# avr.net
KiCad netlist of a schematic drawn in EAGLE
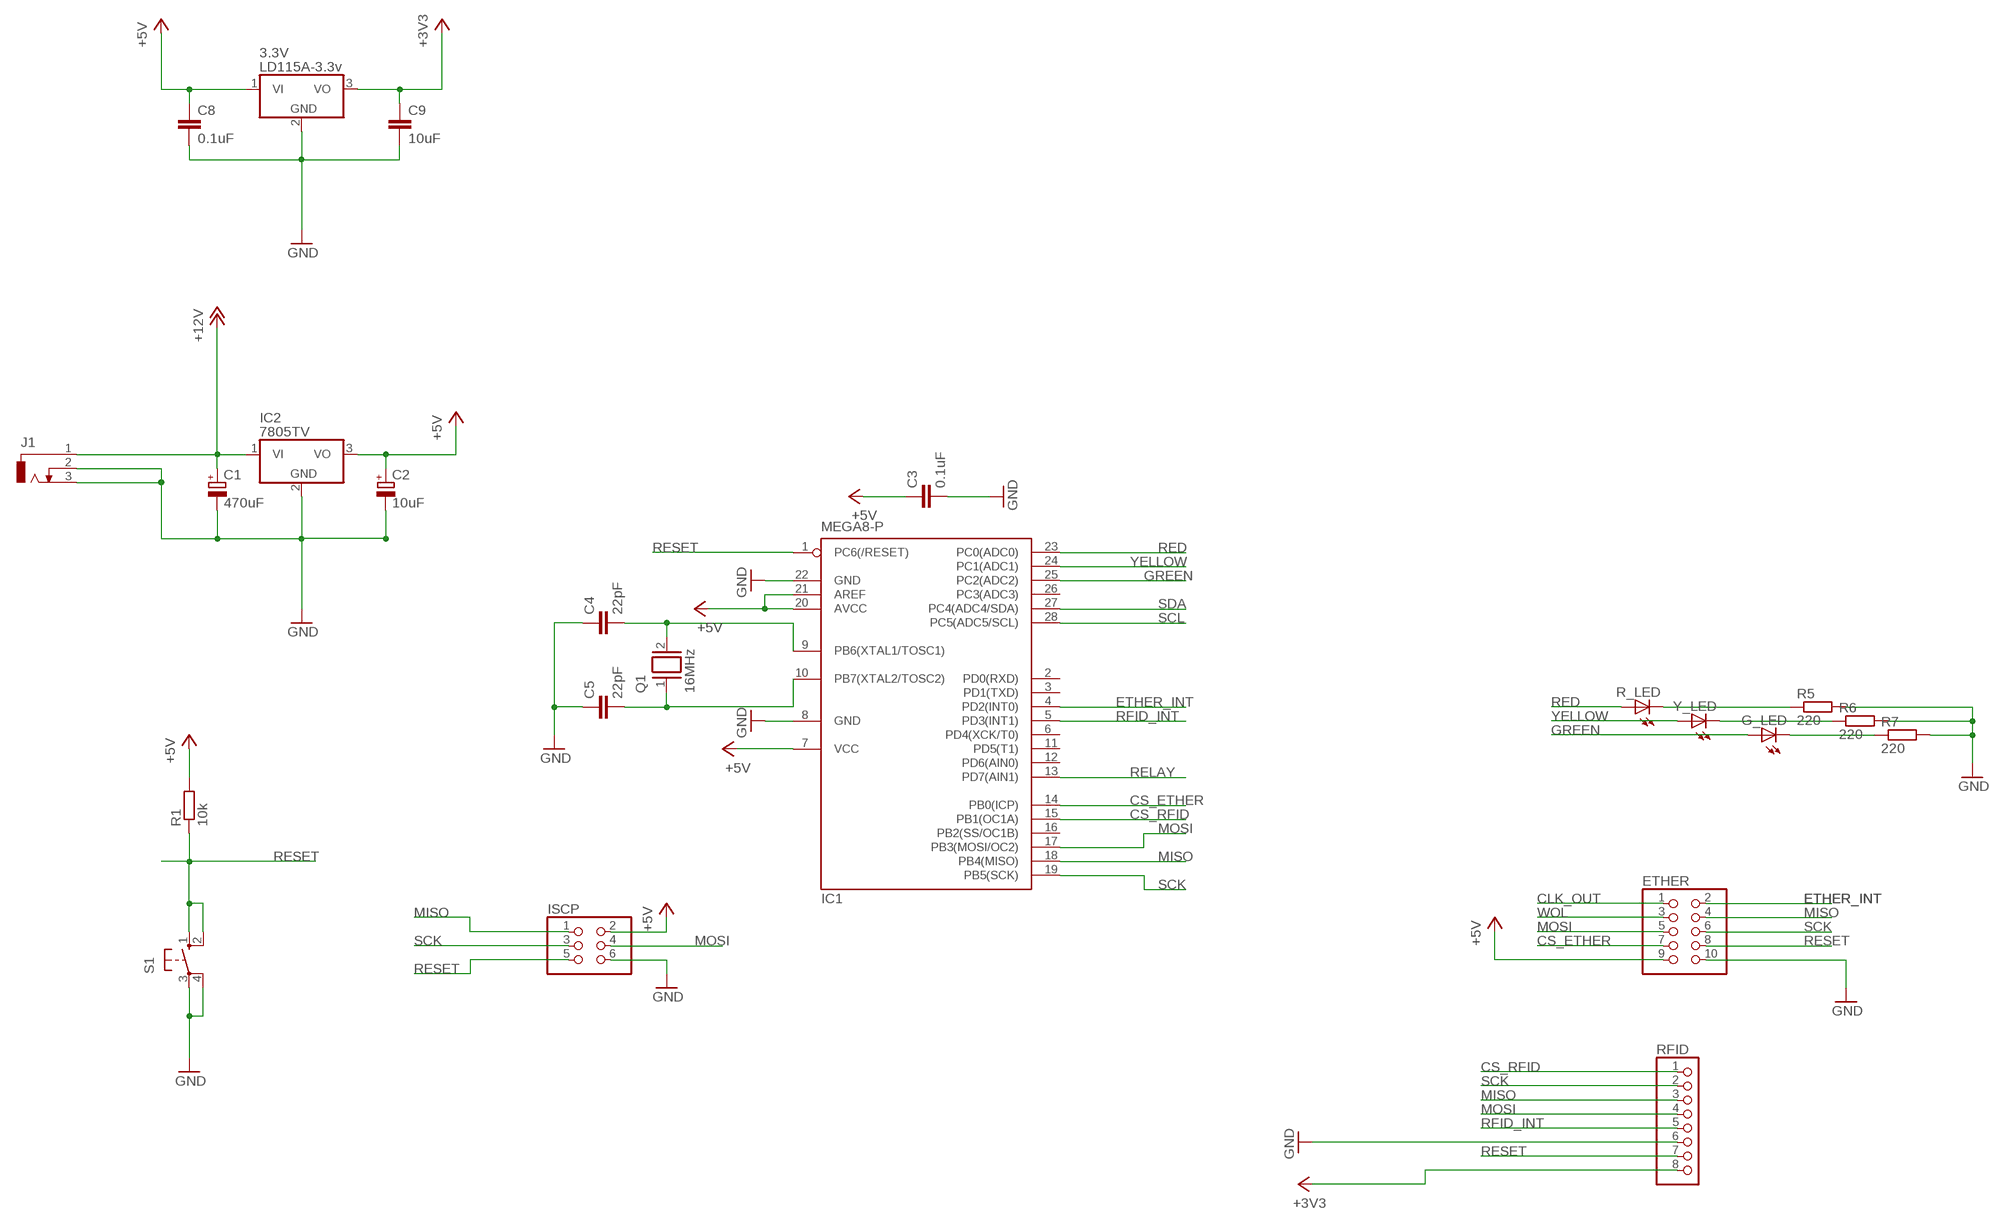
[diagram p0: schematic, sheet 1]

(export (version "E")
  (design (tool "Eeschema 10.0.6"))
  (components
    (comp (ref "3.3V")
      (value "LD115A-3.3v")
      (footprint "eagle-import:TO220V")
      (libsource (lib "eagle-import") (part "78TV05"))
    )
    (comp (ref "C1")
      (value "470uF")
      (footprint "eagle-import:E3,5-10")
      (libsource (lib "eagle-import") (part "CPOL-EUE3.5-10"))
    )
    (comp (ref "C2")
      (value "10uF")
      (footprint "eagle-import:E3,5-10")
      (libsource (lib "eagle-import") (part "CPOL-EUE3.5-10"))
    )
    (comp (ref "C3")
      (value "0.1uF")
      (footprint "eagle-import:C050-025X075")
      (libsource (lib "eagle-import") (part "C-EU050-025X075"))
    )
    (comp (ref "C4")
      (value "22pF")
      (footprint "eagle-import:C050-025X075")
      (libsource (lib "eagle-import") (part "C-EU050-025X075"))
    )
    (comp (ref "C5")
      (value "22pF")
      (footprint "eagle-import:C050-025X075")
      (libsource (lib "eagle-import") (part "C-EU050-025X075"))
    )
    (comp (ref "C8")
      (value "0.1uF")
      (footprint "eagle-import:C050-025X075")
      (libsource (lib "eagle-import") (part "C-EU050-025X075"))
    )
    (comp (ref "C9")
      (value "10uF")
      (footprint "eagle-import:C050-025X075")
      (libsource (lib "eagle-import") (part "C-EU050-025X075"))
    )
    (comp (ref "ETHER")
      (value "PINHD-2X5")
      (footprint "eagle-import:2X05")
      (libsource (lib "eagle-import") (part "PINHD-2X5"))
    )
    (comp (ref "G_LED")
      (value "LED5MM")
      (footprint "eagle-import:LED5MM")
      (libsource (lib "eagle-import") (part "LED5MM"))
    )
    (comp (ref "IC1")
      (value "MEGA8-P")
      (footprint "eagle-import:DIL28-3")
      (libsource (lib "eagle-import") (part "MEGA8-P"))
    )
    (comp (ref "IC2")
      (value "7805TV")
      (footprint "eagle-import:TO220V")
      (libsource (lib "eagle-import") (part "78TV05"))
    )
    (comp (ref "ISCP")
      (value "PINHD-2X3")
      (footprint "eagle-import:2X03")
      (libsource (lib "eagle-import") (part "PINHD-2X3"))
    )
    (comp (ref "J1")
      (value "DCJ0303")
      (footprint "eagle-import:DCJ0303")
      (libsource (lib "eagle-import") (part "DCJ0303"))
    )
    (comp (ref "Q1")
      (value "16MHz")
      (footprint "eagle-import:QS")
      (libsource (lib "eagle-import") (part "XTAL/S"))
    )
    (comp (ref "R1")
      (value "10k")
      (footprint "eagle-import:0207_10")
      (libsource (lib "eagle-import") (part "R-EU_0207/10"))
    )
    (comp (ref "R5")
      (value "220")
      (footprint "eagle-import:0207_10")
      (libsource (lib "eagle-import") (part "R-EU_0207/10"))
    )
    (comp (ref "R6")
      (value "220")
      (footprint "eagle-import:0207_10")
      (libsource (lib "eagle-import") (part "R-EU_0207/10"))
    )
    (comp (ref "R7")
      (value "220")
      (footprint "eagle-import:0207_10")
      (libsource (lib "eagle-import") (part "R-EU_0207/10"))
    )
    (comp (ref "RFID")
      (value "PINHD-1X8")
      (footprint "eagle-import:1X08")
      (libsource (lib "eagle-import") (part "PINHD-1X8"))
    )
    (comp (ref "R_LED")
      (value "LED5MM")
      (footprint "eagle-import:LED5MM")
      (libsource (lib "eagle-import") (part "LED5MM"))
    )
    (comp (ref "S1")
      (value "10-XX")
      (footprint "eagle-import:B3F-10XX")
      (fields (field (name "MPN") "B3F-1000"))
      (libsource (lib "eagle-import") (part "10-XX"))
    )
    (comp (ref "Y_LED")
      (value "LED5MM")
      (footprint "eagle-import:LED5MM")
      (libsource (lib "eagle-import") (part "LED5MM"))
    )
  )
  (nets
    (net (code "1") (name "+3V3") (class "Default")
      (node (ref "3.3V") (pin "3") (pinfunction "VO_3") (pintype "passive"))
      (node (ref "C9") (pin "1") (pinfunction "1_1") (pintype "passive"))
      (node (ref "RFID") (pin "8") (pinfunction "8_8") (pintype "passive"))
    )
    (net (code "2") (name "+5V") (class "Default")
      (node (ref "3.3V") (pin "1") (pinfunction "VI_1") (pintype "input"))
      (node (ref "C2") (pin "+") (pinfunction "+_+") (pintype "passive"))
      (node (ref "C3") (pin "1") (pinfunction "1_1") (pintype "passive"))
      (node (ref "C8") (pin "1") (pinfunction "1_1") (pintype "passive"))
      (node (ref "ETHER") (pin "9") (pinfunction "9_9") (pintype "passive"))
      (node (ref "IC1") (pin "20") (pinfunction "AVCC_20") (pintype "power_in"))
      (node (ref "IC1") (pin "21") (pinfunction "AREF_21") (pintype "passive"))
      (node (ref "IC1") (pin "7") (pinfunction "VCC_7") (pintype "power_in"))
      (node (ref "IC2") (pin "3") (pinfunction "VO_3") (pintype "passive"))
      (node (ref "ISCP") (pin "2") (pinfunction "2_2") (pintype "passive"))
      (node (ref "R1") (pin "2") (pinfunction "2_2") (pintype "passive"))
    )
    (net (code "3") (name "+12V") (class "Default")
      (node (ref "C1") (pin "+") (pinfunction "+_+") (pintype "passive"))
      (node (ref "IC2") (pin "1") (pinfunction "VI_1") (pintype "input"))
      (node (ref "J1") (pin "1") (pinfunction "1_1") (pintype "passive"))
    )
    (net (code "4") (name "/CLK_OUT") (class "Default")
      (node (ref "ETHER") (pin "1") (pinfunction "1_1") (pintype "passive"))
    )
    (net (code "5") (name "/CS_ETHER") (class "Default")
      (node (ref "ETHER") (pin "7") (pinfunction "7_7") (pintype "passive"))
      (node (ref "IC1") (pin "14") (pinfunction "PB0(ICP)_14") (pintype "bidirectional"))
    )
    (net (code "6") (name "/CS_RFID") (class "Default")
      (node (ref "IC1") (pin "15") (pinfunction "PB1(OC1A)_15") (pintype "bidirectional"))
      (node (ref "RFID") (pin "1") (pinfunction "1_1") (pintype "passive"))
    )
    (net (code "7") (name "/ETHER_INT") (class "Default")
      (node (ref "ETHER") (pin "2") (pinfunction "2_2") (pintype "passive"))
      (node (ref "IC1") (pin "4") (pinfunction "PD2(INT0)_4") (pintype "bidirectional"))
    )
    (net (code "8") (name "/GREEN") (class "Default")
      (node (ref "G_LED") (pin "A") (pinfunction "A_A") (pintype "passive"))
      (node (ref "IC1") (pin "25") (pinfunction "PC2(ADC2)_25") (pintype "bidirectional"))
    )
    (net (code "9") (name "/MISO") (class "Default")
      (node (ref "ETHER") (pin "4") (pinfunction "4_4") (pintype "passive"))
      (node (ref "IC1") (pin "18") (pinfunction "PB4(MISO)_18") (pintype "bidirectional"))
      (node (ref "ISCP") (pin "1") (pinfunction "1_1") (pintype "passive"))
      (node (ref "RFID") (pin "3") (pinfunction "3_3") (pintype "passive"))
    )
    (net (code "10") (name "/MOSI") (class "Default")
      (node (ref "ETHER") (pin "5") (pinfunction "5_5") (pintype "passive"))
      (node (ref "IC1") (pin "17") (pinfunction "PB3(MOSI/OC2)_17") (pintype "bidirectional"))
      (node (ref "ISCP") (pin "4") (pinfunction "4_4") (pintype "passive"))
      (node (ref "RFID") (pin "4") (pinfunction "4_4") (pintype "passive"))
    )
    (net (code "11") (name "/RED") (class "Default")
      (node (ref "IC1") (pin "23") (pinfunction "PC0(ADC0)_23") (pintype "bidirectional"))
      (node (ref "R_LED") (pin "A") (pinfunction "A_A") (pintype "passive"))
    )
    (net (code "12") (name "/RELAY") (class "Default")
      (node (ref "IC1") (pin "13") (pinfunction "PD7(AIN1)_13") (pintype "bidirectional"))
    )
    (net (code "13") (name "/RESET") (class "Default")
      (node (ref "ETHER") (pin "8") (pinfunction "8_8") (pintype "passive"))
      (node (ref "IC1") (pin "1") (pinfunction "PC6(/RESET)_1") (pintype "bidirectional"))
      (node (ref "ISCP") (pin "5") (pinfunction "5_5") (pintype "passive"))
      (node (ref "R1") (pin "1") (pinfunction "1_1") (pintype "passive"))
      (node (ref "RFID") (pin "7") (pinfunction "7_7") (pintype "passive"))
      (node (ref "S1") (pin "1") (pinfunction "S_1") (pintype "passive"))
      (node (ref "S1") (pin "2") (pinfunction "S1_2") (pintype "passive"))
    )
    (net (code "14") (name "/RFID_INT") (class "Default")
      (node (ref "IC1") (pin "5") (pinfunction "PD3(INT1)_5") (pintype "bidirectional"))
      (node (ref "RFID") (pin "5") (pinfunction "5_5") (pintype "passive"))
    )
    (net (code "15") (name "/SCK") (class "Default")
      (node (ref "ETHER") (pin "6") (pinfunction "6_6") (pintype "passive"))
      (node (ref "IC1") (pin "19") (pinfunction "PB5(SCK)_19") (pintype "bidirectional"))
      (node (ref "ISCP") (pin "3") (pinfunction "3_3") (pintype "passive"))
      (node (ref "RFID") (pin "2") (pinfunction "2_2") (pintype "passive"))
    )
    (net (code "16") (name "/SCL") (class "Default")
      (node (ref "IC1") (pin "28") (pinfunction "PC5(ADC5/SCL)_28") (pintype "bidirectional"))
    )
    (net (code "17") (name "/SDA") (class "Default")
      (node (ref "IC1") (pin "27") (pinfunction "PC4(ADC4/SDA)_27") (pintype "bidirectional"))
    )
    (net (code "18") (name "/WOL") (class "Default")
      (node (ref "ETHER") (pin "3") (pinfunction "3_3") (pintype "passive"))
    )
    (net (code "19") (name "/YELLOW") (class "Default")
      (node (ref "IC1") (pin "24") (pinfunction "PC1(ADC1)_24") (pintype "bidirectional"))
      (node (ref "Y_LED") (pin "A") (pinfunction "A_A") (pintype "passive"))
    )
    (net (code "20") (name "GND") (class "Default")
      (node (ref "3.3V") (pin "2") (pinfunction "GND_2") (pintype "passive"))
      (node (ref "C1") (pin "-") (pinfunction "-_-") (pintype "passive"))
      (node (ref "C2") (pin "-") (pinfunction "-_-") (pintype "passive"))
      (node (ref "C3") (pin "2") (pinfunction "2_2") (pintype "passive"))
      (node (ref "C4") (pin "1") (pinfunction "1_1") (pintype "passive"))
      (node (ref "C5") (pin "1") (pinfunction "1_1") (pintype "passive"))
      (node (ref "C8") (pin "2") (pinfunction "2_2") (pintype "passive"))
      (node (ref "C9") (pin "2") (pinfunction "2_2") (pintype "passive"))
      (node (ref "ETHER") (pin "10") (pinfunction "10_10") (pintype "passive"))
      (node (ref "IC1") (pin "22") (pinfunction "GND_22") (pintype "power_in"))
      (node (ref "IC1") (pin "8") (pinfunction "GND_8") (pintype "power_in"))
      (node (ref "IC2") (pin "2") (pinfunction "GND_2") (pintype "passive"))
      (node (ref "ISCP") (pin "6") (pinfunction "6_6") (pintype "passive"))
      (node (ref "J1") (pin "2") (pinfunction "2_2") (pintype "passive"))
      (node (ref "J1") (pin "3") (pinfunction "3_3") (pintype "passive"))
      (node (ref "R5") (pin "2") (pinfunction "2_2") (pintype "passive"))
      (node (ref "R6") (pin "2") (pinfunction "2_2") (pintype "passive"))
      (node (ref "R7") (pin "2") (pinfunction "2_2") (pintype "passive"))
      (node (ref "RFID") (pin "6") (pinfunction "6_6") (pintype "passive"))
      (node (ref "S1") (pin "3") (pinfunction "P_3") (pintype "passive"))
      (node (ref "S1") (pin "4") (pinfunction "P1_4") (pintype "passive"))
    )
    (net (code "21") (name "Net-(G_LED-C)") (class "Default")
      (node (ref "G_LED") (pin "K") (pinfunction "C_K") (pintype "passive"))
      (node (ref "R7") (pin "1") (pinfunction "1_1") (pintype "passive"))
    )
    (net (code "22") (name "Net-(IC1-PB6(XTAL1{slash}TOSC1))") (class "Default")
      (node (ref "C4") (pin "2") (pinfunction "2_2") (pintype "passive"))
      (node (ref "IC1") (pin "9") (pinfunction "PB6(XTAL1/TOSC1)_9") (pintype "bidirectional"))
      (node (ref "Q1") (pin "2") (pinfunction "2_2") (pintype "passive"))
    )
    (net (code "23") (name "Net-(IC1-PB7(XTAL2{slash}TOSC2))") (class "Default")
      (node (ref "C5") (pin "2") (pinfunction "2_2") (pintype "passive"))
      (node (ref "IC1") (pin "10") (pinfunction "PB7(XTAL2/TOSC2)_10") (pintype "bidirectional"))
      (node (ref "Q1") (pin "1") (pinfunction "1_1") (pintype "passive"))
    )
    (net (code "24") (name "Net-(R_LED-C)") (class "Default")
      (node (ref "R5") (pin "1") (pinfunction "1_1") (pintype "passive"))
      (node (ref "R_LED") (pin "K") (pinfunction "C_K") (pintype "passive"))
    )
    (net (code "25") (name "Net-(Y_LED-C)") (class "Default")
      (node (ref "R6") (pin "1") (pinfunction "1_1") (pintype "passive"))
      (node (ref "Y_LED") (pin "K") (pinfunction "C_K") (pintype "passive"))
    )
    (net (code "26") (name "unconnected-(IC1-PB2(SS{slash}OC1B)-Pad16)") (class "Default")
      (node (ref "IC1") (pin "16") (pinfunction "PB2(SS/OC1B)_16") (pintype "bidirectional"))
    )
    (net (code "27") (name "unconnected-(IC1-PC3(ADC3)-Pad26)") (class "Default")
      (node (ref "IC1") (pin "26") (pinfunction "PC3(ADC3)_26") (pintype "bidirectional"))
    )
    (net (code "28") (name "unconnected-(IC1-PD0(RXD)-Pad2)") (class "Default")
      (node (ref "IC1") (pin "2") (pinfunction "PD0(RXD)_2") (pintype "bidirectional"))
    )
    (net (code "29") (name "unconnected-(IC1-PD1(TXD)-Pad3)") (class "Default")
      (node (ref "IC1") (pin "3") (pinfunction "PD1(TXD)_3") (pintype "bidirectional"))
    )
    (net (code "30") (name "unconnected-(IC1-PD4(XCK{slash}T0)-Pad6)") (class "Default")
      (node (ref "IC1") (pin "6") (pinfunction "PD4(XCK/T0)_6") (pintype "bidirectional"))
    )
    (net (code "31") (name "unconnected-(IC1-PD5(T1)-Pad11)") (class "Default")
      (node (ref "IC1") (pin "11") (pinfunction "PD5(T1)_11") (pintype "bidirectional"))
    )
    (net (code "32") (name "unconnected-(IC1-PD6(AIN0)-Pad12)") (class "Default")
      (node (ref "IC1") (pin "12") (pinfunction "PD6(AIN0)_12") (pintype "bidirectional"))
    )
  )
)
